# 03_Mechanicals.net
KiCad netlist of a schematic drawn in Altium Designer
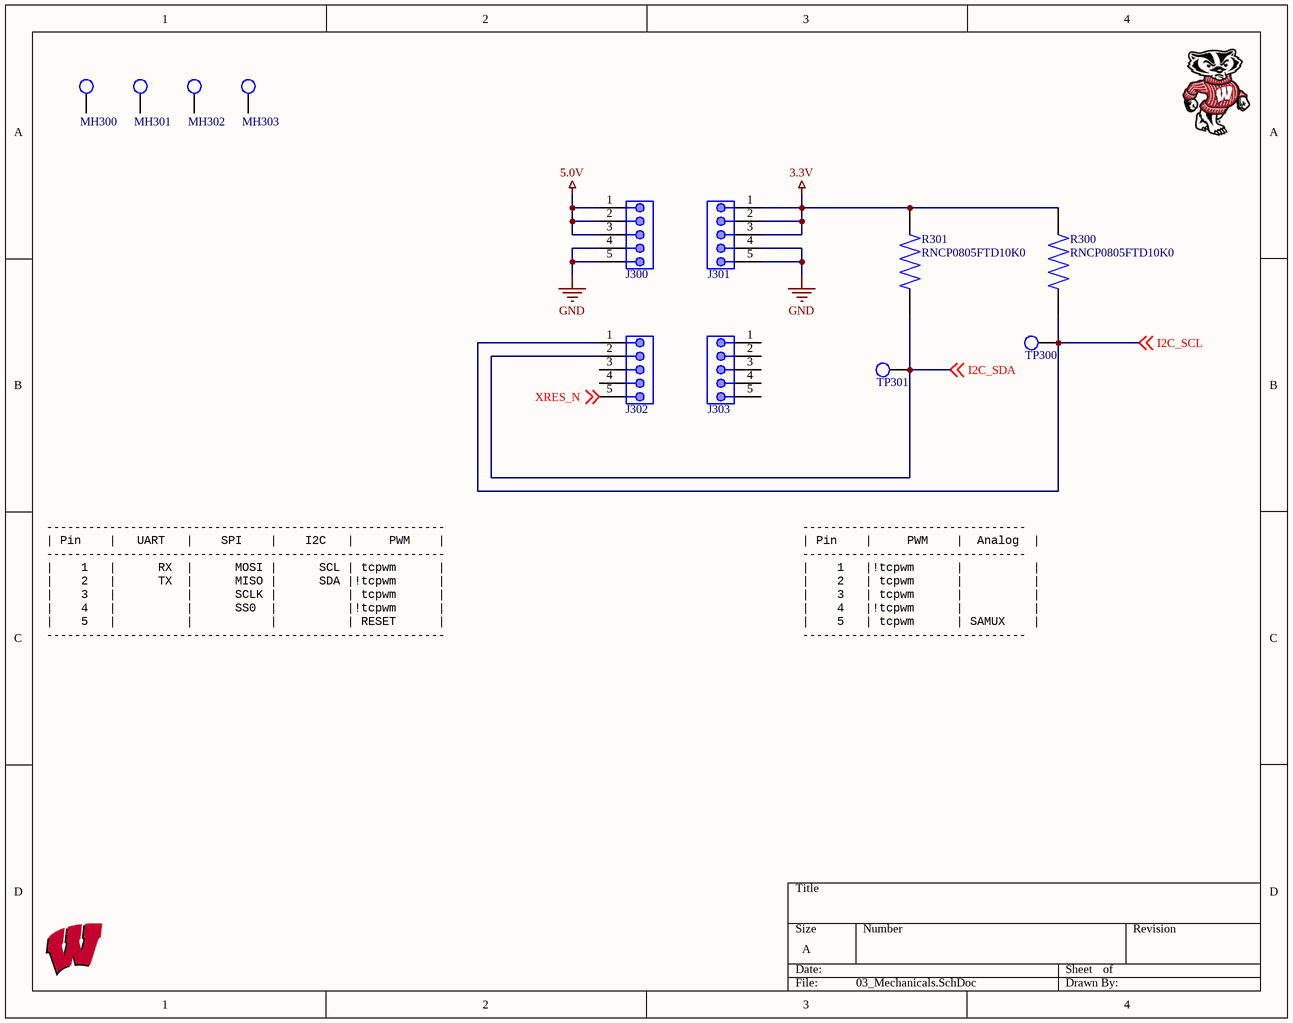
[diagram p0: 03_Mechanicals.SchDoc]

(export (version "E")
  (design (tool "Eeschema 10.0.6"))
  (components
    (comp (ref "J300")
      (value "CONN_HEADER_MALE_1x5")
      (footprint "HDR1X5")
      (description "Header, 5-Pin")
      (libsource (lib "Connectors") (part "CONN_HEADER_MALE_1x5"))
    )
    (comp (ref "J301")
      (value "CONN_HEADER_MALE_1x5")
      (footprint "HDR1X5")
      (description "Header, 5-Pin")
      (libsource (lib "") (part "CONN_HEADER_MALE_1x5_1"))
    )
    (comp (ref "J302")
      (value "CONN_HEADER_MALE_1x5")
      (footprint "HDR1X5")
      (description "Header, 5-Pin")
      (libsource (lib "Connectors") (part "CONN_HEADER_MALE_1x5"))
    )
    (comp (ref "J303")
      (value "CONN_HEADER_MALE_1x5")
      (footprint "HDR1X5")
      (description "Header, 5-Pin")
      (libsource (lib "") (part "CONN_HEADER_MALE_1x5_1"))
    )
    (comp (ref "MH300")
      (value "MHOLE_2_55MM")
      (footprint "MHOLE_2_55MM")
      (description "Mounting Holde")
      (fields (field (name "MANUFACTURER PART NUMBER") "UW MTHOLE"))
      (libsource (lib "ece315-2018-fall") (part "MHOLE_2_55MM"))
    )
    (comp (ref "MH301")
      (value "MHOLE_2_55MM")
      (footprint "MHOLE_2_55MM")
      (description "Mounting Holde")
      (fields (field (name "MANUFACTURER PART NUMBER") "UW MTHOLE"))
      (libsource (lib "ece315-2018-fall") (part "MHOLE_2_55MM"))
    )
    (comp (ref "MH302")
      (value "MHOLE_2_55MM")
      (footprint "MHOLE_2_55MM")
      (description "Mounting Holde")
      (fields (field (name "MANUFACTURER PART NUMBER") "UW MTHOLE"))
      (libsource (lib "ece315-2018-fall") (part "MHOLE_2_55MM"))
    )
    (comp (ref "MH303")
      (value "MHOLE_2_55MM")
      (footprint "MHOLE_2_55MM")
      (description "Mounting Holde")
      (fields (field (name "MANUFACTURER PART NUMBER") "UW MTHOLE"))
      (libsource (lib "ece315-2018-fall") (part "MHOLE_2_55MM"))
    )
    (comp (ref "R300")
      (value "RNCP0805FTD10K0")
      (footprint "RESC2012X60N")
      (fields
        (field (name "DIGI-KEY_PART_NUMBER") "RNCP0805FTD10K0CT-ND")
        (field (name "MF") "Stackpole Electronics Inc")
      )
      (libsource (lib "chess_module") (part "RNCP0805FTD10K0"))
    )
    (comp (ref "R301")
      (value "RNCP0805FTD10K0")
      (footprint "RESC2012X60N")
      (fields
        (field (name "DIGI-KEY_PART_NUMBER") "RNCP0805FTD10K0CT-ND")
        (field (name "MF") "Stackpole Electronics Inc")
      )
      (libsource (lib "chess_module") (part "RNCP0805FTD10K0"))
    )
    (comp (ref "TP300")
      (value "TP_1206")
      (footprint "TP-SMC-1206")
      (description "Test Point SMD 1206")
      (fields
        (field (name "MANUFACTURER") "TE Connectivity (Tyco Electronics)")
        (field (name "MANUFACTURER PART NUMBER") "1625854-1")
      )
      (libsource (lib "ECE453-F22-Power") (part "TP_1206"))
    )
    (comp (ref "TP301")
      (value "TP_1206")
      (footprint "TP-SMC-1206")
      (description "Test Point SMD 1206")
      (fields
        (field (name "MANUFACTURER") "TE Connectivity (Tyco Electronics)")
        (field (name "MANUFACTURER PART NUMBER") "1625854-1")
      )
      (libsource (lib "ECE453-F22-Power") (part "TP_1206"))
    )
  )
  (nets
    (net (code "1") (name "3.3V") (class "Default")
      (node (ref "J301") (pin "1") (pinfunction "1_1") (pintype "passive"))
      (node (ref "J301") (pin "2") (pinfunction "2_2") (pintype "passive"))
      (node (ref "J301") (pin "3") (pinfunction "3_3") (pintype "passive"))
      (node (ref "R300") (pin "2") (pinfunction "2_2") (pintype "passive"))
      (node (ref "R301") (pin "2") (pinfunction "2_2") (pintype "passive"))
    )
    (net (code "2") (name "5.0V") (class "Default")
      (node (ref "J300") (pin "1") (pinfunction "1_1") (pintype "passive"))
      (node (ref "J300") (pin "2") (pinfunction "2_2") (pintype "passive"))
      (node (ref "J300") (pin "3") (pinfunction "3_3") (pintype "passive"))
    )
    (net (code "3") (name "GND") (class "Default")
      (node (ref "J300") (pin "4") (pinfunction "4_4") (pintype "passive"))
      (node (ref "J300") (pin "5") (pinfunction "5_5") (pintype "passive"))
      (node (ref "J301") (pin "4") (pinfunction "4_4") (pintype "passive"))
      (node (ref "J301") (pin "5") (pinfunction "5_5") (pintype "passive"))
    )
    (net (code "4") (name "I2C_SCL") (class "Default")
      (node (ref "J302") (pin "1") (pinfunction "1_1") (pintype "passive"))
      (node (ref "R300") (pin "1") (pinfunction "1_1") (pintype "passive"))
      (node (ref "TP300") (pin "1") (pintype "passive"))
    )
    (net (code "5") (name "I2C_SDA") (class "Default")
      (node (ref "J302") (pin "2") (pinfunction "2_2") (pintype "passive"))
      (node (ref "R301") (pin "1") (pinfunction "1_1") (pintype "passive"))
      (node (ref "TP301") (pin "1") (pintype "passive"))
    )
    (net (code "6") (name "XRES_N") (class "Default")
      (node (ref "J302") (pin "5") (pinfunction "5_5") (pintype "passive"))
    )
    (net (code "7") (name "unconnected-(J302-Pad3)") (class "Default")
      (node (ref "J302") (pin "3") (pinfunction "3_3") (pintype "passive"))
    )
    (net (code "8") (name "unconnected-(J302-Pad4)") (class "Default")
      (node (ref "J302") (pin "4") (pinfunction "4_4") (pintype "passive"))
    )
    (net (code "9") (name "unconnected-(J303-Pad1)") (class "Default")
      (node (ref "J303") (pin "1") (pinfunction "1_1") (pintype "passive"))
    )
    (net (code "10") (name "unconnected-(J303-Pad2)") (class "Default")
      (node (ref "J303") (pin "2") (pinfunction "2_2") (pintype "passive"))
    )
    (net (code "11") (name "unconnected-(J303-Pad3)") (class "Default")
      (node (ref "J303") (pin "3") (pinfunction "3_3") (pintype "passive"))
    )
    (net (code "12") (name "unconnected-(J303-Pad4)") (class "Default")
      (node (ref "J303") (pin "4") (pinfunction "4_4") (pintype "passive"))
    )
    (net (code "13") (name "unconnected-(J303-Pad5)") (class "Default")
      (node (ref "J303") (pin "5") (pinfunction "5_5") (pintype "passive"))
    )
    (net (code "14") (name "unconnected-(MH300-Pad1)") (class "Default")
      (node (ref "MH300") (pin "1") (pintype "passive"))
    )
    (net (code "15") (name "unconnected-(MH301-Pad1)") (class "Default")
      (node (ref "MH301") (pin "1") (pintype "passive"))
    )
    (net (code "16") (name "unconnected-(MH302-Pad1)") (class "Default")
      (node (ref "MH302") (pin "1") (pintype "passive"))
    )
    (net (code "17") (name "unconnected-(MH303-Pad1)") (class "Default")
      (node (ref "MH303") (pin "1") (pintype "passive"))
    )
  )
)
